# AlarmShield.net
KiCad netlist of a schematic drawn in Altium Designer
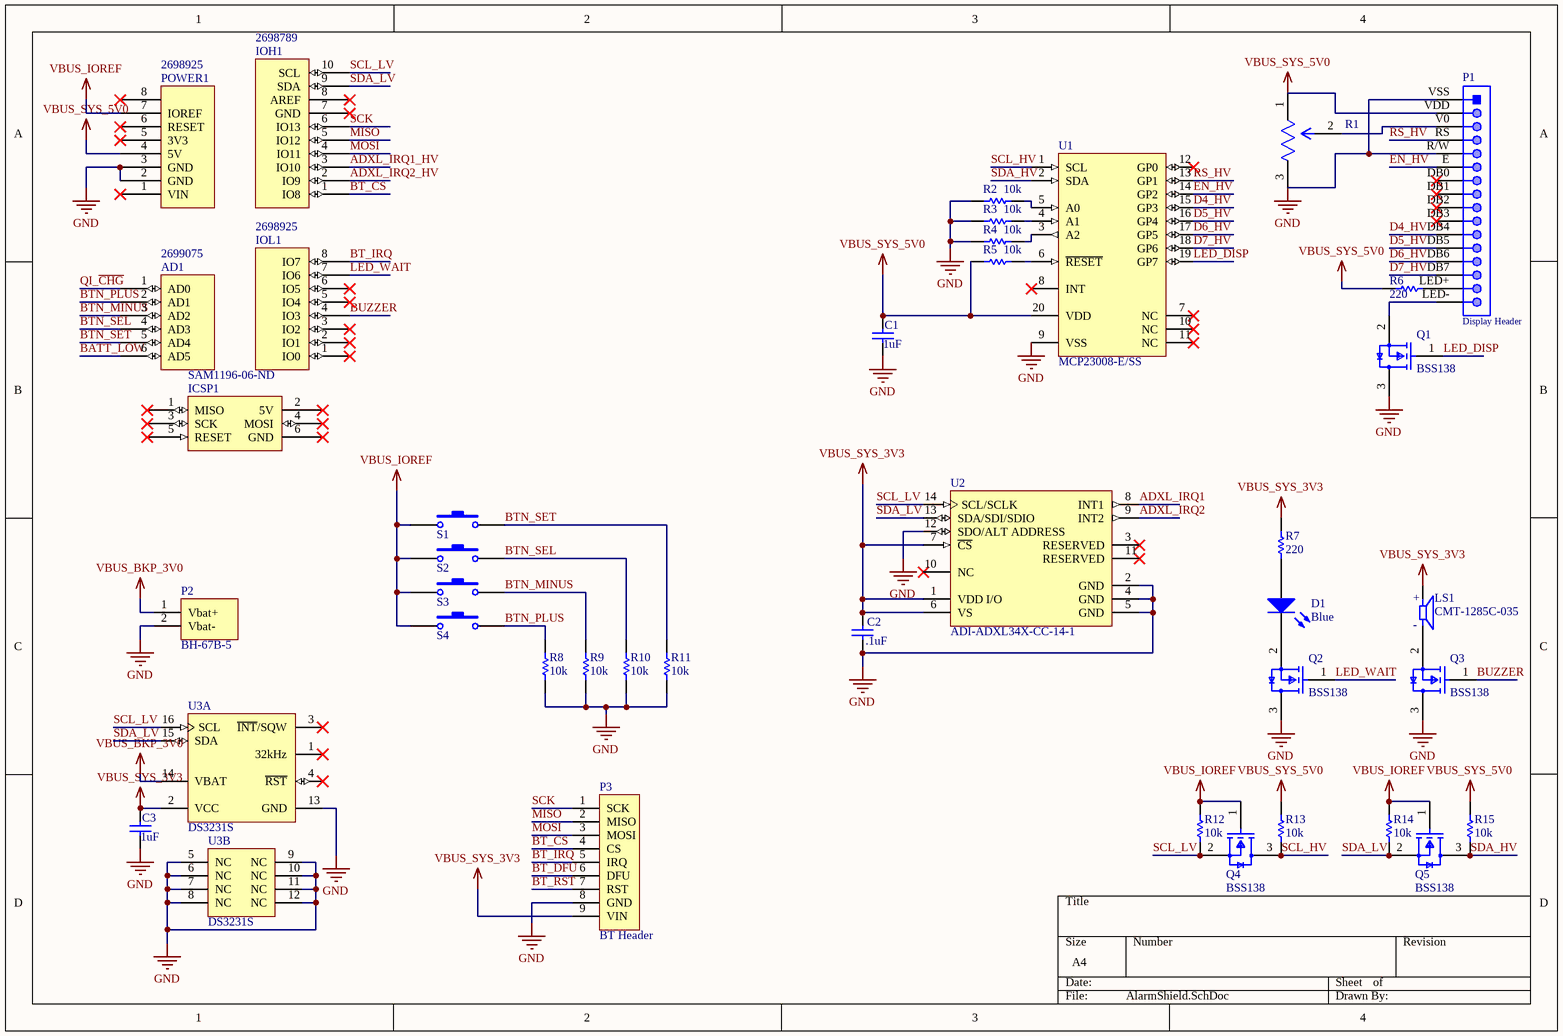
[diagram p0: AlarmShield.SchDoc]

(export (version "E")
  (design (tool "Eeschema 10.0.6"))
  (components
    (comp (ref "AD1")
      (value "AD")
      (footprint "Header:Header 6x1 8.5mm")
      (fields (field (name "SUPPLIER PART NUMBER 4") "2699075"))
      (libsource (lib "Header") (part "AD"))
    )
    (comp (ref "C1")
      (value "1uF")
      (footprint "0805")
      (description "1.5nF, 10%, 50V")
      (fields (field (name "GFUPARTNO") "CC0805KRX7R9BB152"))
      (libsource (lib "AltiumGFU") (part "Cap"))
    )
    (comp (ref "C2")
      (value ".1uF")
      (footprint "0805")
      (description "1.5nF, 10%, 50V")
      (fields (field (name "GFUPARTNO") "CC0805KRX7R9BB152"))
      (libsource (lib "AltiumGFU") (part "Cap"))
    )
    (comp (ref "C3")
      (value "1uF")
      (footprint "0805")
      (description "1.5nF, 10%, 50V")
      (fields (field (name "GFUPARTNO") "CC0805KRX7R9BB152"))
      (libsource (lib "AltiumGFU") (part "Cap"))
    )
    (comp (ref "D1")
      (value "Blue")
      (footprint "1206_A_LED")
      (libsource (lib "Altium Content Vault") (part "WE-LED_K1A2-2_Local"))
    )
    (comp (ref "ICSP1")
      (value "ICSP")
      (footprint "ICSP")
      (fields (field (name "SUPPLIER PART NUMBER 5") "SAM1196-06-ND"))
      (libsource (lib "Header") (part "ICSP"))
    )
    (comp (ref "IOH1")
      (value "IOH")
      (footprint "Header:Header 10x1 8.5mm")
      (fields (field (name "SUPPLIER PART NUMBER 3") "2698789"))
      (libsource (lib "Header") (part "IOH"))
    )
    (comp (ref "IOL1")
      (value "IOL")
      (footprint "Header 8x1 8.5mm")
      (fields (field (name "SUPPLIER PART NUMBER 4") "2698925"))
      (libsource (lib "Header") (part "IOL"))
    )
    (comp (ref "LS1")
      (value "CMT-1285C-035")
      (footprint "CUI_CMT-1285C-035")
      (description "12 mm, 3.5 Vo-p, 91 dB, Through Hole, Magnetic Audio Transducer Buzzer")
      (fields (field (name "MF") "CUI Devices"))
      (libsource (lib "CMT-1285C-035") (part "CMT-1285C-035"))
    )
    (comp (ref "P1")
      (value "Display Header")
      (footprint "61301611121")
      (description "THT Vertical Pin Header WR-PHD, Pitch 2.54 mm, Single Row, 16 pins")
      (fields
        (field (name "PART NUMBER") "61301611121")
        (field (name "MANUFACTURER") "Wurth Elektronik")
        (field (name "PUBLISHER") "WurthElektronik")
      )
      (libsource (lib "Altium Content Vault") (part "WE-CN-1P-M-R16"))
    )
    (comp (ref "P2")
      (value "BH-67B-5")
      (footprint "PCBComponent_1")
      (description "BATTERY HOLDER CR 2032")
      (libsource (lib "BatteryHolder") (part "BH-67B-5"))
    )
    (comp (ref "P3")
      (value "BT Header")
      (footprint "HDR1X9")
      (description "Header, 9-Pin")
      (fields (field (name "PUBLISHER") "Altium Limited"))
      (libsource (lib "Miscellaneous Connectors") (part "Header 9"))
    )
    (comp (ref "POWER1")
      (value "POWER_UNO")
      (footprint "Header 8x1 8.5mm")
      (fields (field (name "SUPPLIER PART NUMBER 4") "2698925"))
      (libsource (lib "Header") (part "POWER_UNO"))
    )
    (comp (ref "Q1")
      (value "BSS138")
      (footprint "FP-318-08-IPC_B")
      (description "MOSFET N-CH 50V 220MA SOT-23")
      (libsource (lib "Altium Content Vault") (part "3b9c635fedb024a5347a57b145af9cc"))
    )
    (comp (ref "Q2")
      (value "BSS138")
      (footprint "FP-318-08-IPC_B")
      (description "MOSFET N-CH 50V 220MA SOT-23")
      (libsource (lib "Altium Content Vault") (part "3b9c635fedb024a5347a57b145af9cc"))
    )
    (comp (ref "Q3")
      (value "BSS138")
      (footprint "FP-318-08-IPC_B")
      (description "MOSFET N-CH 50V 220MA SOT-23")
      (libsource (lib "Altium Content Vault") (part "3b9c635fedb024a5347a57b145af9cc"))
    )
    (comp (ref "Q4")
      (value "BSS138")
      (footprint "FP-318-08-IPC_B")
      (description "MOSFET N-CH 50V 220MA SOT-23")
      (libsource (lib "Altium Content Vault") (part "3b9c635fedb024a5347a57b145af9cc"))
    )
    (comp (ref "Q5")
      (value "BSS138")
      (footprint "FP-318-08-IPC_B")
      (description "MOSFET N-CH 50V 220MA SOT-23")
      (libsource (lib "Altium Content Vault") (part "3b9c635fedb024a5347a57b145af9cc"))
    )
    (comp (ref "R1")
      (value "100k")
      (footprint "FP-3386T-MFG")
      (description "Contrast Trim Potentiometer")
      (libsource (lib "ContrastPot") (part "3386T_1_103TLF"))
    )
    (comp (ref "R2")
      (value "10k")
      (footprint "0805_RES_HD")
      (description "50k Ohm ±1% 0.125W, 1/8W Surface Mount Resistor Thick Film ±100ppm/°C 0805")
      (fields (field (name "GFUPARTNO") "RC0805FR-07100RL"))
      (libsource (lib "AltiumGFU") (part "ResBasic"))
    )
    (comp (ref "R3")
      (value "10k")
      (footprint "0805_RES_HD")
      (description "50k Ohm ±1% 0.125W, 1/8W Surface Mount Resistor Thick Film ±100ppm/°C 0805")
      (fields (field (name "GFUPARTNO") "RC0805FR-07100RL"))
      (libsource (lib "AltiumGFU") (part "ResBasic"))
    )
    (comp (ref "R4")
      (value "10k")
      (footprint "0805_RES_HD")
      (description "50k Ohm ±1% 0.125W, 1/8W Surface Mount Resistor Thick Film ±100ppm/°C 0805")
      (fields (field (name "GFUPARTNO") "RC0805FR-07100RL"))
      (libsource (lib "AltiumGFU") (part "ResBasic"))
    )
    (comp (ref "R5")
      (value "10k")
      (footprint "0805_RES_HD")
      (description "50k Ohm ±1% 0.125W, 1/8W Surface Mount Resistor Thick Film ±100ppm/°C 0805")
      (fields (field (name "GFUPARTNO") "RC0805FR-07100RL"))
      (libsource (lib "AltiumGFU") (part "ResBasic"))
    )
    (comp (ref "R6")
      (value "220")
      (footprint "0805_RES_HD")
      (description "50k Ohm ±1% 0.125W, 1/8W Surface Mount Resistor Thick Film ±100ppm/°C 0805")
      (fields (field (name "GFUPARTNO") "RC0805FR-07100RL"))
      (libsource (lib "AltiumGFU") (part "ResBasic"))
    )
    (comp (ref "R7")
      (value "220")
      (footprint "0805_RES_HD")
      (description "50k Ohm ±1% 0.125W, 1/8W Surface Mount Resistor Thick Film ±100ppm/°C 0805")
      (fields (field (name "GFUPARTNO") "RC0805FR-07100RL"))
      (libsource (lib "AltiumGFU") (part "ResBasic"))
    )
    (comp (ref "R8")
      (value "10k")
      (footprint "0805_RES_HD")
      (description "50k Ohm ±1% 0.125W, 1/8W Surface Mount Resistor Thick Film ±100ppm/°C 0805")
      (fields (field (name "GFUPARTNO") "RC0805FR-07100RL"))
      (libsource (lib "AltiumGFU") (part "ResBasic"))
    )
    (comp (ref "R9")
      (value "10k")
      (footprint "0805_RES_HD")
      (description "50k Ohm ±1% 0.125W, 1/8W Surface Mount Resistor Thick Film ±100ppm/°C 0805")
      (fields (field (name "GFUPARTNO") "RC0805FR-07100RL"))
      (libsource (lib "AltiumGFU") (part "ResBasic"))
    )
    (comp (ref "R10")
      (value "10k")
      (footprint "0805_RES_HD")
      (description "50k Ohm ±1% 0.125W, 1/8W Surface Mount Resistor Thick Film ±100ppm/°C 0805")
      (fields (field (name "GFUPARTNO") "RC0805FR-07100RL"))
      (libsource (lib "AltiumGFU") (part "ResBasic"))
    )
    (comp (ref "R11")
      (value "10k")
      (footprint "0805_RES_HD")
      (description "50k Ohm ±1% 0.125W, 1/8W Surface Mount Resistor Thick Film ±100ppm/°C 0805")
      (fields (field (name "GFUPARTNO") "RC0805FR-07100RL"))
      (libsource (lib "AltiumGFU") (part "ResBasic"))
    )
    (comp (ref "R12")
      (value "10k")
      (footprint "0805_RES_HD")
      (description "50k Ohm ±1% 0.125W, 1/8W Surface Mount Resistor Thick Film ±100ppm/°C 0805")
      (fields (field (name "GFUPARTNO") "RC0805FR-07100RL"))
      (libsource (lib "AltiumGFU") (part "ResBasic"))
    )
    (comp (ref "R13")
      (value "10k")
      (footprint "0805_RES_HD")
      (description "50k Ohm ±1% 0.125W, 1/8W Surface Mount Resistor Thick Film ±100ppm/°C 0805")
      (fields (field (name "GFUPARTNO") "RC0805FR-07100RL"))
      (libsource (lib "AltiumGFU") (part "ResBasic"))
    )
    (comp (ref "R14")
      (value "10k")
      (footprint "0805_RES_HD")
      (description "50k Ohm ±1% 0.125W, 1/8W Surface Mount Resistor Thick Film ±100ppm/°C 0805")
      (fields (field (name "GFUPARTNO") "RC0805FR-07100RL"))
      (libsource (lib "AltiumGFU") (part "ResBasic"))
    )
    (comp (ref "R15")
      (value "10k")
      (footprint "0805_RES_HD")
      (description "50k Ohm ±1% 0.125W, 1/8W Surface Mount Resistor Thick Film ±100ppm/°C 0805")
      (fields (field (name "GFUPARTNO") "RC0805FR-07100RL"))
      (libsource (lib "AltiumGFU") (part "ResBasic"))
    )
    (comp (ref "S1")
      (value "KSC221J")
      (footprint "ITT Cannon KSC2 Series")
      (description "SWITCH TACT SILVER J-LEAD")
      (libsource (lib "AltiumGFU") (part "SW-PB"))
    )
    (comp (ref "S2")
      (value "KSC221J")
      (footprint "ITT Cannon KSC2 Series")
      (description "SWITCH TACT SILVER J-LEAD")
      (libsource (lib "AltiumGFU") (part "SW-PB"))
    )
    (comp (ref "S3")
      (value "KSC221J")
      (footprint "ITT Cannon KSC2 Series")
      (description "SWITCH TACT SILVER J-LEAD")
      (libsource (lib "AltiumGFU") (part "SW-PB"))
    )
    (comp (ref "S4")
      (value "KSC221J")
      (footprint "ITT Cannon KSC2 Series")
      (description "SWITCH TACT SILVER J-LEAD")
      (libsource (lib "AltiumGFU") (part "SW-PB"))
    )
    (comp (ref "U1")
      (value "MCP23008-E/SS")
      (footprint "SSOP-SS20_N")
      (description "8-Bit I/O Expander with Serial Interface, 20-Pin SSOP, Extended Temperature")
      (libsource (lib "Altium Content Vault") (part "PR-BUSIC-MCP23008-20"))
    )
    (comp (ref "U2")
      (value "ADI-ADXL34X-CC-14-1")
      (footprint "ADXL")
      (libsource (lib "ADXL") (part "ADI-ADXL34X-CC-14-1"))
    )
    (comp (ref "U3")
      (value "DS3231S")
      (footprint "W16-H2_L")
      (description "Extremely Accurate I2C-Integrated Real-Time Clock/TCXO/Crystal, 16-Pin SO, 0 to 70 degC")
      (libsource (lib "Altium Content Vault") (part "MAX-RTC-16-DS3231S-W16#H2"))
    )
  )
  (nets
    (net (code "2") (name "/ADXL_IRQ1") (class "Default")
      (node (ref "U2") (pin "8") (pinfunction "INT1_8") (pintype "output"))
    )
    (net (code "3") (name "/ADXL_IRQ1_HV") (class "Default")
      (node (ref "IOH1") (pin "3") (pinfunction "IO10_3") (pintype "bidirectional"))
    )
    (net (code "4") (name "/ADXL_IRQ2") (class "Default")
      (node (ref "U2") (pin "9") (pinfunction "INT2_9") (pintype "output"))
    )
    (net (code "5") (name "/ADXL_IRQ2_HV") (class "Default")
      (node (ref "IOH1") (pin "2") (pinfunction "IO9_2") (pintype "bidirectional"))
    )
    (net (code "6") (name "/BATT_LOW") (class "Default")
      (node (ref "AD1") (pin "6") (pinfunction "AD5_6") (pintype "bidirectional"))
    )
    (net (code "7") (name "/BTN_MINUS") (class "Default")
      (node (ref "AD1") (pin "3") (pinfunction "AD2_3") (pintype "bidirectional"))
      (node (ref "R9") (pin "2") (pinfunction "2_2") (pintype "passive"))
      (node (ref "S3") (pin "2") (pinfunction "2_2") (pintype "passive"))
    )
    (net (code "8") (name "/BTN_PLUS") (class "Default")
      (node (ref "AD1") (pin "2") (pinfunction "AD1_2") (pintype "bidirectional"))
      (node (ref "R8") (pin "2") (pinfunction "2_2") (pintype "passive"))
      (node (ref "S4") (pin "2") (pinfunction "2_2") (pintype "passive"))
    )
    (net (code "9") (name "/BTN_SEL") (class "Default")
      (node (ref "AD1") (pin "4") (pinfunction "AD3_4") (pintype "bidirectional"))
      (node (ref "R10") (pin "2") (pinfunction "2_2") (pintype "passive"))
      (node (ref "S2") (pin "2") (pinfunction "2_2") (pintype "passive"))
    )
    (net (code "10") (name "/BTN_SET") (class "Default")
      (node (ref "AD1") (pin "5") (pinfunction "AD4_5") (pintype "bidirectional"))
      (node (ref "R11") (pin "2") (pinfunction "2_2") (pintype "passive"))
      (node (ref "S1") (pin "2") (pinfunction "2_2") (pintype "passive"))
    )
    (net (code "11") (name "/BT_CS") (class "Default")
      (node (ref "IOH1") (pin "1") (pinfunction "IO8_1") (pintype "bidirectional"))
      (node (ref "P3") (pin "4") (pinfunction "CS_4") (pintype "passive"))
    )
    (net (code "12") (name "/BT_DFU") (class "Default")
      (node (ref "P3") (pin "6") (pinfunction "DFU_6") (pintype "passive"))
    )
    (net (code "13") (name "/BT_IRQ") (class "Default")
      (node (ref "IOL1") (pin "8") (pinfunction "IO7_8") (pintype "bidirectional"))
      (node (ref "P3") (pin "5") (pinfunction "IRQ_5") (pintype "passive"))
    )
    (net (code "14") (name "/BT_RST") (class "Default")
      (node (ref "P3") (pin "7") (pinfunction "RST_7") (pintype "passive"))
    )
    (net (code "15") (name "/BUZZER") (class "Default")
      (node (ref "IOL1") (pin "4") (pinfunction "IO3_4") (pintype "bidirectional"))
      (node (ref "Q3") (pin "1") (pinfunction "G_1") (pintype "passive"))
    )
    (net (code "16") (name "/D4_HV") (class "Default")
      (node (ref "P1") (pin "DB4") (pinfunction "11_DB4") (pintype "passive"))
      (node (ref "U1") (pin "15") (pinfunction "GP3_15") (pintype "bidirectional"))
    )
    (net (code "17") (name "/D5_HV") (class "Default")
      (node (ref "P1") (pin "DB5") (pinfunction "12_DB5") (pintype "passive"))
      (node (ref "U1") (pin "16") (pinfunction "GP4_16") (pintype "bidirectional"))
    )
    (net (code "18") (name "/D6_HV") (class "Default")
      (node (ref "P1") (pin "DB6") (pinfunction "13_DB6") (pintype "passive"))
      (node (ref "U1") (pin "17") (pinfunction "GP5_17") (pintype "bidirectional"))
    )
    (net (code "19") (name "/D7_HV") (class "Default")
      (node (ref "P1") (pin "DB7") (pinfunction "14_DB7") (pintype "passive"))
      (node (ref "U1") (pin "18") (pinfunction "GP6_18") (pintype "bidirectional"))
    )
    (net (code "20") (name "/EN_HV") (class "Default")
      (node (ref "P1") (pin "E") (pinfunction "6_E") (pintype "passive"))
      (node (ref "U1") (pin "14") (pinfunction "GP2_14") (pintype "bidirectional"))
    )
    (net (code "21") (name "/LED_DISP") (class "Default")
      (node (ref "Q1") (pin "1") (pinfunction "G_1") (pintype "passive"))
      (node (ref "U1") (pin "19") (pinfunction "GP7_19") (pintype "bidirectional"))
    )
    (net (code "22") (name "/LED_WAIT") (class "Default")
      (node (ref "IOL1") (pin "7") (pinfunction "IO6_7") (pintype "bidirectional"))
      (node (ref "Q2") (pin "1") (pinfunction "G_1") (pintype "passive"))
    )
    (net (code "23") (name "/MISO") (class "Default")
      (node (ref "IOH1") (pin "5") (pinfunction "IO12_5") (pintype "bidirectional"))
      (node (ref "P3") (pin "2") (pinfunction "MISO_2") (pintype "passive"))
    )
    (net (code "24") (name "/MOSI") (class "Default")
      (node (ref "IOH1") (pin "4") (pinfunction "IO11_4") (pintype "bidirectional"))
      (node (ref "P3") (pin "3") (pinfunction "MOSI_3") (pintype "passive"))
    )
    (net (code "25") (name "/QI_~{CHG}") (class "Default")
      (node (ref "AD1") (pin "1") (pinfunction "AD0_1") (pintype "bidirectional"))
    )
    (net (code "26") (name "/RS_HV") (class "Default")
      (node (ref "P1") (pin "RS") (pinfunction "4_RS") (pintype "passive"))
      (node (ref "U1") (pin "13") (pinfunction "GP1_13") (pintype "bidirectional"))
    )
    (net (code "27") (name "/SCK") (class "Default")
      (node (ref "IOH1") (pin "6") (pinfunction "IO13_6") (pintype "bidirectional"))
      (node (ref "P3") (pin "1") (pinfunction "SCK_1") (pintype "passive"))
    )
    (net (code "28") (name "/SCL_HV") (class "Default")
      (node (ref "Q4") (pin "3") (pinfunction "D_3") (pintype "passive"))
      (node (ref "R13") (pin "2") (pinfunction "2_2") (pintype "passive"))
      (node (ref "U1") (pin "1") (pinfunction "SCL_1") (pintype "input"))
    )
    (net (code "29") (name "/SCL_LV") (class "Default")
      (node (ref "IOH1") (pin "10") (pinfunction "SCL_10") (pintype "bidirectional"))
      (node (ref "Q4") (pin "2") (pinfunction "S_2") (pintype "passive"))
      (node (ref "R12") (pin "2") (pinfunction "2_2") (pintype "passive"))
      (node (ref "U2") (pin "14") (pinfunction "SCL/SCLK_14") (pintype "input"))
      (node (ref "U3") (pin "16") (pinfunction "SCL_16") (pintype "input"))
    )
    (net (code "30") (name "/SDA_HV") (class "Default")
      (node (ref "Q5") (pin "3") (pinfunction "D_3") (pintype "passive"))
      (node (ref "R15") (pin "2") (pinfunction "2_2") (pintype "passive"))
      (node (ref "U1") (pin "2") (pinfunction "SDA_2") (pintype "input"))
    )
    (net (code "31") (name "/SDA_LV") (class "Default")
      (node (ref "IOH1") (pin "9") (pinfunction "SDA_9") (pintype "bidirectional"))
      (node (ref "Q5") (pin "2") (pinfunction "S_2") (pintype "passive"))
      (node (ref "R14") (pin "2") (pinfunction "2_2") (pintype "passive"))
      (node (ref "U2") (pin "13") (pinfunction "SDA/SDI/SDIO_13") (pintype "bidirectional"))
      (node (ref "U3") (pin "15") (pinfunction "SDA_15") (pintype "bidirectional"))
    )
    (net (code "32") (name "GND") (class "Default")
      (node (ref "C1") (pin "2") (pinfunction "2_2") (pintype "passive"))
      (node (ref "C2") (pin "2") (pinfunction "2_2") (pintype "passive"))
      (node (ref "C3") (pin "2") (pinfunction "2_2") (pintype "passive"))
      (node (ref "P1") (pin "R/W") (pinfunction "5_R/W") (pintype "passive"))
      (node (ref "P1") (pin "VSS") (pinfunction "1_VSS") (pintype "passive"))
      (node (ref "P2") (pin "2") (pinfunction "Vbat-_2") (pintype "power_in"))
      (node (ref "P3") (pin "8") (pinfunction "GND_8") (pintype "passive"))
      (node (ref "POWER1") (pin "2") (pinfunction "GND_2") (pintype "power_in"))
      (node (ref "POWER1") (pin "3") (pinfunction "GND_3") (pintype "power_in"))
      (node (ref "Q1") (pin "3") (pinfunction "D_3") (pintype "passive"))
      (node (ref "Q2") (pin "3") (pinfunction "D_3") (pintype "passive"))
      (node (ref "Q3") (pin "3") (pinfunction "D_3") (pintype "passive"))
      (node (ref "R1") (pin "3") (pinfunction "CW_3") (pintype "passive"))
      (node (ref "R10") (pin "1") (pinfunction "1_1") (pintype "passive"))
      (node (ref "R11") (pin "1") (pinfunction "1_1") (pintype "passive"))
      (node (ref "R2") (pin "2") (pinfunction "2_2") (pintype "passive"))
      (node (ref "R3") (pin "2") (pinfunction "2_2") (pintype "passive"))
      (node (ref "R4") (pin "2") (pinfunction "2_2") (pintype "passive"))
      (node (ref "R8") (pin "1") (pinfunction "1_1") (pintype "passive"))
      (node (ref "R9") (pin "1") (pinfunction "1_1") (pintype "passive"))
      (node (ref "U1") (pin "9") (pinfunction "VSS_9") (pintype "power_in"))
      (node (ref "U2") (pin "12") (pinfunction "SDO/ALT_ADDRESS_12") (pintype "bidirectional"))
      (node (ref "U2") (pin "2") (pinfunction "GND_2") (pintype "power_in"))
      (node (ref "U2") (pin "4") (pinfunction "GND_4") (pintype "power_in"))
      (node (ref "U2") (pin "5") (pinfunction "GND_5") (pintype "power_in"))
      (node (ref "U3") (pin "10") (pinfunction "NC_10") (pintype "passive"))
      (node (ref "U3") (pin "11") (pinfunction "NC_11") (pintype "passive"))
      (node (ref "U3") (pin "12") (pinfunction "NC_12") (pintype "passive"))
      (node (ref "U3") (pin "13") (pinfunction "GND_13") (pintype "power_in"))
      (node (ref "U3") (pin "5") (pinfunction "NC_5") (pintype "passive"))
      (node (ref "U3") (pin "6") (pinfunction "NC_6") (pintype "passive"))
      (node (ref "U3") (pin "7") (pinfunction "NC_7") (pintype "passive"))
      (node (ref "U3") (pin "8") (pinfunction "NC_8") (pintype "passive"))
      (node (ref "U3") (pin "9") (pinfunction "NC_9") (pintype "passive"))
    )
    (net (code "33") (name "Net-(D1-A)") (class "Default")
      (node (ref "D1") (pin "2") (pinfunction "A_2") (pintype "passive"))
      (node (ref "R7") (pin "1") (pinfunction "1_1") (pintype "passive"))
    )
    (net (code "34") (name "Net-(D1-K)") (class "Default")
      (node (ref "D1") (pin "1") (pinfunction "K_1") (pintype "passive"))
      (node (ref "Q2") (pin "2") (pinfunction "S_2") (pintype "passive"))
    )
    (net (code "35") (name "Net-(P1-3)") (class "Default")
      (node (ref "P1") (pin "V0") (pinfunction "3_V0") (pintype "passive"))
      (node (ref "R1") (pin "2") (pinfunction "WIPER_2") (pintype "passive"))
    )
    (net (code "36") (name "Net-(P1-15)") (class "Default")
      (node (ref "P1") (pin "LED+") (pinfunction "15_LED+") (pintype "passive"))
      (node (ref "R6") (pin "2") (pinfunction "2_2") (pintype "passive"))
    )
    (net (code "37") (name "Net-(P1-16)") (class "Default")
      (node (ref "P1") (pin "LED-") (pinfunction "16_LED-") (pintype "passive"))
      (node (ref "Q1") (pin "2") (pinfunction "S_2") (pintype "passive"))
    )
    (net (code "38") (name "Net-(Q3-S)") (class "Default")
      (node (ref "LS1") (pin "N") (pinfunction "N_N") (pintype "passive"))
      (node (ref "Q3") (pin "2") (pinfunction "S_2") (pintype "passive"))
    )
    (net (code "39") (name "Net-(U1-A0)") (class "Default")
      (node (ref "R2") (pin "1") (pinfunction "1_1") (pintype "passive"))
      (node (ref "U1") (pin "5") (pinfunction "A0_5") (pintype "input"))
    )
    (net (code "40") (name "Net-(U1-A1)") (class "Default")
      (node (ref "R3") (pin "1") (pinfunction "1_1") (pintype "passive"))
      (node (ref "U1") (pin "4") (pinfunction "A1_4") (pintype "input"))
    )
    (net (code "41") (name "Net-(U1-A2)") (class "Default")
      (node (ref "R4") (pin "1") (pinfunction "1_1") (pintype "passive"))
      (node (ref "U1") (pin "3") (pinfunction "A2_3") (pintype "output"))
    )
    (net (code "42") (name "Net-(U1-~{RESET})") (class "Default")
      (node (ref "R5") (pin "1") (pinfunction "1_1") (pintype "passive"))
      (node (ref "U1") (pin "6") (pinfunction "~{RESET}_6") (pintype "input"))
    )
    (net (code "43") (name "VBUS_BKP_3V0") (class "Default")
      (node (ref "P2") (pin "1") (pinfunction "Vbat+_1") (pintype "power_in"))
      (node (ref "U3") (pin "14") (pinfunction "VBAT_14") (pintype "power_in"))
    )
    (net (code "44") (name "VBUS_IOREF") (class "Default")
      (node (ref "POWER1") (pin "7") (pinfunction "IOREF_7") (pintype "power_in"))
      (node (ref "Q4") (pin "1") (pinfunction "G_1") (pintype "passive"))
      (node (ref "Q5") (pin "1") (pinfunction "G_1") (pintype "passive"))
      (node (ref "R12") (pin "1") (pinfunction "1_1") (pintype "passive"))
      (node (ref "R14") (pin "1") (pinfunction "1_1") (pintype "passive"))
      (node (ref "S1") (pin "1") (pinfunction "1_1") (pintype "passive"))
      (node (ref "S2") (pin "1") (pinfunction "1_1") (pintype "passive"))
      (node (ref "S3") (pin "1") (pinfunction "1_1") (pintype "passive"))
      (node (ref "S4") (pin "1") (pinfunction "1_1") (pintype "passive"))
    )
    (net (code "45") (name "VBUS_SYS_3V3") (class "Default")
      (node (ref "C2") (pin "1") (pinfunction "1_1") (pintype "passive"))
      (node (ref "C3") (pin "1") (pinfunction "1_1") (pintype "passive"))
      (node (ref "LS1") (pin "P") (pinfunction "P_P") (pintype "passive"))
      (node (ref "P3") (pin "9") (pinfunction "VIN_9") (pintype "passive"))
      (node (ref "R7") (pin "2") (pinfunction "2_2") (pintype "passive"))
      (node (ref "U2") (pin "1") (pinfunction "VDD_I/O_1") (pintype "power_in"))
      (node (ref "U2") (pin "6") (pinfunction "VS_6") (pintype "power_in"))
      (node (ref "U2") (pin "7") (pinfunction "~{CS}_7") (pintype "input"))
      (node (ref "U3") (pin "2") (pinfunction "VCC_2") (pintype "power_in"))
    )
    (net (code "46") (name "VBUS_SYS_5V0") (class "Default")
      (node (ref "C1") (pin "1") (pinfunction "1_1") (pintype "passive"))
      (node (ref "P1") (pin "VDD") (pinfunction "2_VDD") (pintype "passive"))
      (node (ref "POWER1") (pin "4") (pinfunction "5V_4") (pintype "power_in"))
      (node (ref "R1") (pin "1") (pinfunction "CCW_1") (pintype "passive"))
      (node (ref "R13") (pin "1") (pinfunction "1_1") (pintype "passive"))
      (node (ref "R15") (pin "1") (pinfunction "1_1") (pintype "passive"))
      (node (ref "R5") (pin "2") (pinfunction "2_2") (pintype "passive"))
      (node (ref "R6") (pin "1") (pinfunction "1_1") (pintype "passive"))
      (node (ref "U1") (pin "20") (pinfunction "VDD_20") (pintype "power_in"))
    )
    (net (code "47") (name "unconnected-(ICSP1-5V-Pad2)") (class "Default")
      (node (ref "ICSP1") (pin "2") (pinfunction "5V_2") (pintype "power_in+no_connect"))
    )
    (net (code "48") (name "unconnected-(ICSP1-GND-Pad6)") (class "Default")
      (node (ref "ICSP1") (pin "6") (pinfunction "GND_6") (pintype "power_in+no_connect"))
    )
    (net (code "49") (name "unconnected-(ICSP1-MISO-Pad1)") (class "Default")
      (node (ref "ICSP1") (pin "1") (pinfunction "MISO_1") (pintype "bidirectional+no_connect"))
    )
    (net (code "50") (name "unconnected-(ICSP1-MOSI-Pad4)") (class "Default")
      (node (ref "ICSP1") (pin "4") (pinfunction "MOSI_4") (pintype "bidirectional+no_connect"))
    )
    (net (code "51") (name "unconnected-(ICSP1-RESET-Pad5)") (class "Default")
      (node (ref "ICSP1") (pin "5") (pinfunction "RESET_5") (pintype "input+no_connect"))
    )
    (net (code "52") (name "unconnected-(ICSP1-SCK-Pad3)") (class "Default")
      (node (ref "ICSP1") (pin "3") (pinfunction "SCK_3") (pintype "bidirectional+no_connect"))
    )
    (net (code "53") (name "unconnected-(IOH1-AREF-Pad8)") (class "Default")
      (node (ref "IOH1") (pin "8") (pinfunction "AREF_8") (pintype "passive+no_connect"))
    )
    (net (code "54") (name "unconnected-(IOH1-GND-Pad7)") (class "Default")
      (node (ref "IOH1") (pin "7") (pinfunction "GND_7") (pintype "power_in+no_connect"))
    )
    (net (code "55") (name "unconnected-(IOL1-IO0-Pad1)") (class "Default")
      (node (ref "IOL1") (pin "1") (pinfunction "IO0_1") (pintype "bidirectional+no_connect"))
    )
    (net (code "56") (name "unconnected-(IOL1-IO1-Pad2)") (class "Default")
      (node (ref "IOL1") (pin "2") (pinfunction "IO1_2") (pintype "bidirectional+no_connect"))
    )
    (net (code "57") (name "unconnected-(IOL1-IO2-Pad3)") (class "Default")
      (node (ref "IOL1") (pin "3") (pinfunction "IO2_3") (pintype "bidirectional+no_connect"))
    )
    (net (code "58") (name "unconnected-(IOL1-IO4-Pad5)") (class "Default")
      (node (ref "IOL1") (pin "5") (pinfunction "IO4_5") (pintype "bidirectional+no_connect"))
    )
    (net (code "59") (name "unconnected-(IOL1-IO5-Pad6)") (class "Default")
      (node (ref "IOL1") (pin "6") (pinfunction "IO5_6") (pintype "bidirectional+no_connect"))
    )
    (net (code "60") (name "unconnected-(P1-7-PadDB0)") (class "Default")
      (node (ref "P1") (pin "DB0") (pinfunction "7_DB0") (pintype "passive+no_connect"))
    )
    (net (code "61") (name "unconnected-(P1-8-PadDB1)") (class "Default")
      (node (ref "P1") (pin "DB1") (pinfunction "8_DB1") (pintype "passive+no_connect"))
    )
    (net (code "62") (name "unconnected-(P1-9-PadDB2)") (class "Default")
      (node (ref "P1") (pin "DB2") (pinfunction "9_DB2") (pintype "passive+no_connect"))
    )
    (net (code "63") (name "unconnected-(P1-10-PadDB3)") (class "Default")
      (node (ref "P1") (pin "DB3") (pinfunction "10_DB3") (pintype "passive+no_connect"))
    )
    (net (code "64") (name "unconnected-(POWER1-3V3-Pad5)") (class "Default")
      (node (ref "POWER1") (pin "5") (pinfunction "3V3_5") (pintype "power_in+no_connect"))
    )
    (net (code "65") (name "unconnected-(POWER1-Pad8)") (class "Default")
      (node (ref "POWER1") (pin "8") (pintype "passive+no_connect"))
    )
    (net (code "66") (name "unconnected-(POWER1-RESET-Pad6)") (class "Default")
      (node (ref "POWER1") (pin "6") (pinfunction "RESET_6") (pintype "passive+no_connect"))
    )
    (net (code "67") (name "unconnected-(POWER1-VIN-Pad1)") (class "Default")
      (node (ref "POWER1") (pin "1") (pinfunction "VIN_1") (pintype "power_in+no_connect"))
    )
    (net (code "68") (name "unconnected-(U1-GP0-Pad12)") (class "Default")
      (node (ref "U1") (pin "12") (pinfunction "GP0_12") (pintype "bidirectional+no_connect"))
    )
    (net (code "69") (name "unconnected-(U1-INT-Pad8)") (class "Default")
      (node (ref "U1") (pin "8") (pinfunction "INT_8") (pintype "open_collector+no_connect"))
    )
    (net (code "70") (name "unconnected-(U1-NC-Pad7)") (class "Default")
      (node (ref "U1") (pin "7") (pinfunction "NC_7") (pintype "passive+no_connect"))
    )
    (net (code "71") (name "unconnected-(U1-NC-Pad10)") (class "Default")
      (node (ref "U1") (pin "10") (pinfunction "NC_10") (pintype "passive+no_connect"))
    )
    (net (code "72") (name "unconnected-(U1-NC-Pad11)") (class "Default")
      (node (ref "U1") (pin "11") (pinfunction "NC_11") (pintype "passive+no_connect"))
    )
    (net (code "73") (name "unconnected-(U2-NC-Pad10)") (class "Default")
      (node (ref "U2") (pin "10") (pinfunction "NC_10") (pintype "passive+no_connect"))
    )
    (net (code "74") (name "unconnected-(U2-RESERVED-Pad3)") (class "Default")
      (node (ref "U2") (pin "3") (pinfunction "RESERVED_3") (pintype "passive+no_connect"))
    )
    (net (code "75") (name "unconnected-(U2-RESERVED-Pad11)") (class "Default")
      (node (ref "U2") (pin "11") (pinfunction "RESERVED_11") (pintype "passive+no_connect"))
    )
    (net (code "76") (name "unconnected-(U3A-32kHz-Pad1)") (class "Default")
      (node (ref "U3") (pin "1") (pinfunction "32kHz_1") (pintype "open_collector+no_connect"))
    )
    (net (code "77") (name "unconnected-(U3A-~{INT}{slash}SQW-Pad3)") (class "Default")
      (node (ref "U3") (pin "3") (pinfunction "~{INT}/SQW_3") (pintype "open_collector+no_connect"))
    )
    (net (code "78") (name "unconnected-(U3A-~{RST}-Pad4)") (class "Default")
      (node (ref "U3") (pin "4") (pinfunction "~{RST}_4") (pintype "bidirectional+no_connect"))
    )
  )
)
